# PT-SA.net
KiCad netlist of a schematic drawn in EAGLE
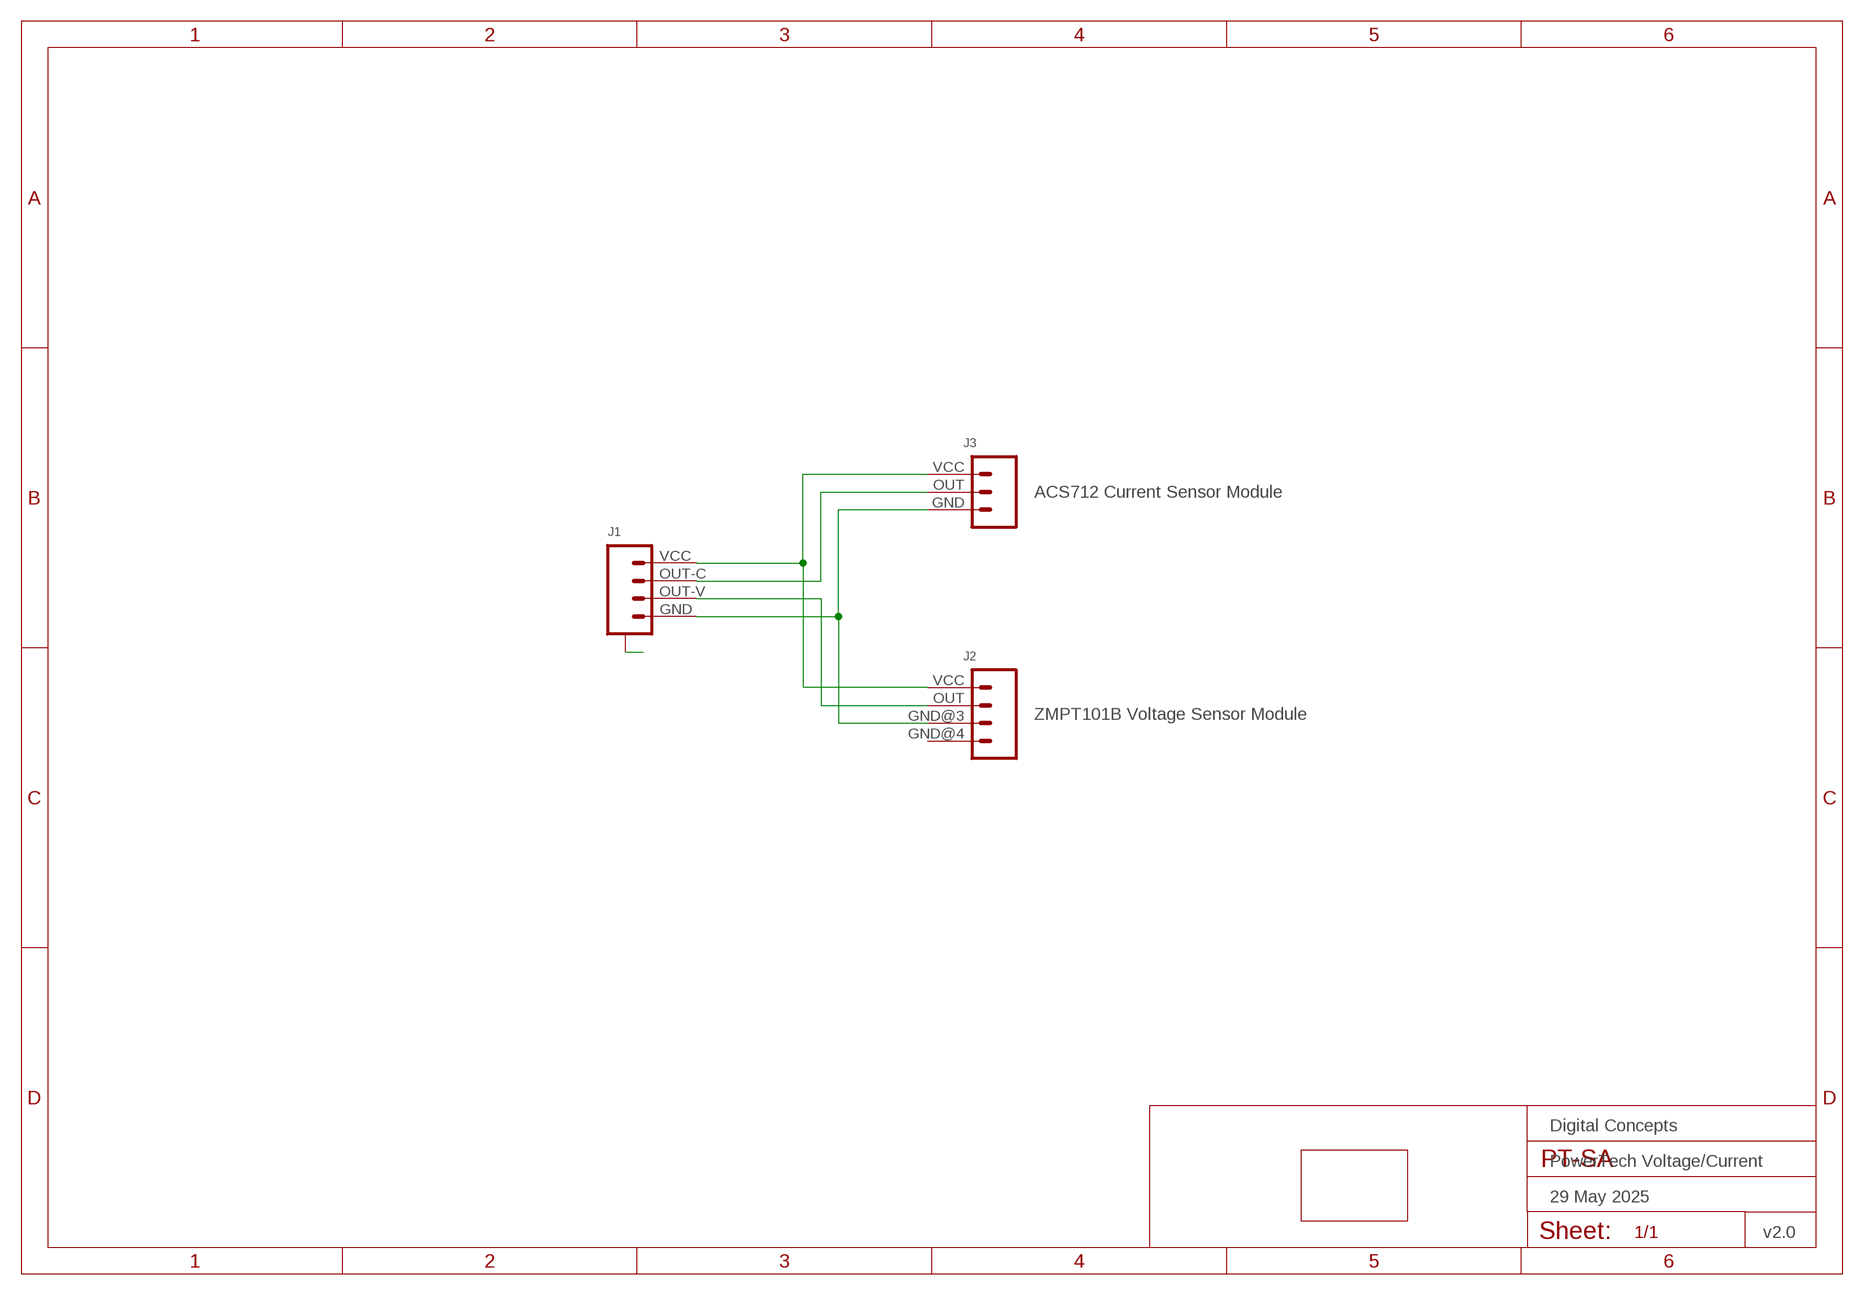
[diagram p0: schematic, sheet 1]

(export (version "E")
  (design (tool "Eeschema 10.0.6"))
  (components
    (comp (ref "J1")
      (value "JST-SH1.0-4-SMD-HORIZONTAL-POWERTECH")
      (footprint "eagle-import:JST-SH1.0-4-HORIZONTAL-POWERTECH")
      (libsource (lib "eagle-import") (part "JST-SH1.0-4-SMD-HORIZONTAL-POWERTECH"))
    )
    (comp (ref "J2")
      (value "ZMPT101B Voltage Sensor Module")
      (footprint "eagle-import:CONN_04-ZMPT101B")
      (libsource (lib "eagle-import") (part "HEADER-1X4-ZMPT101B"))
    )
    (comp (ref "J3")
      (value "ACS712 Current Sensor Module")
      (footprint "eagle-import:CONN_03-ACS712")
      (libsource (lib "eagle-import") (part "HEADER-1X3-ACS712"))
    )
    (comp (ref "PCB1")
      (value "POWERTECH-SOCKET")
      (footprint "eagle-import:PCB-POWERTECH")
      (libsource (lib "eagle-import") (part "POWERTECH-SOCKET"))
    )
  )
  (nets
    (net (code "1") (name "Net-(J1-1)") (class "Default")
      (node (ref "J1") (pin "VCC") (pinfunction "1_VCC") (pintype "passive"))
      (node (ref "J2") (pin "VCC") (pinfunction "1_VCC") (pintype "passive"))
      (node (ref "J3") (pin "VCC") (pinfunction "1_VCC") (pintype "passive"))
    )
    (net (code "2") (name "Net-(J1-2)") (class "Default")
      (node (ref "J1") (pin "OUT-C") (pinfunction "2_OUT-C") (pintype "passive"))
      (node (ref "J3") (pin "OUT") (pinfunction "2_OUT") (pintype "passive"))
    )
    (net (code "3") (name "Net-(J1-3)") (class "Default")
      (node (ref "J1") (pin "OUT-V") (pinfunction "3_OUT-V") (pintype "passive"))
      (node (ref "J2") (pin "OUT") (pinfunction "2_OUT") (pintype "passive"))
    )
    (net (code "4") (name "Net-(J1-4)") (class "Default")
      (node (ref "J1") (pin "GND") (pinfunction "4_GND") (pintype "passive"))
      (node (ref "J2") (pin "GND@3") (pinfunction "3_GND@3") (pintype "passive"))
      (node (ref "J3") (pin "GND") (pinfunction "3_GND") (pintype "passive"))
    )
    (net (code "5") (name "Net-(J1-A-PadA@1)") (class "Default")
      (node (ref "J1") (pin "A@1") (pinfunction "A_A@1") (pintype "power_in"))
      (node (ref "J1") (pin "A@4") (pinfunction "A_A@4") (pintype "power_in"))
    )
    (net (code "6") (name "unconnected-(J2-4-PadGND@4)") (class "Default")
      (node (ref "J2") (pin "GND@4") (pinfunction "4_GND@4") (pintype "passive"))
    )
  )
)
